# untitled.net
KiCad netlist of a schematic drawn in EAGLE
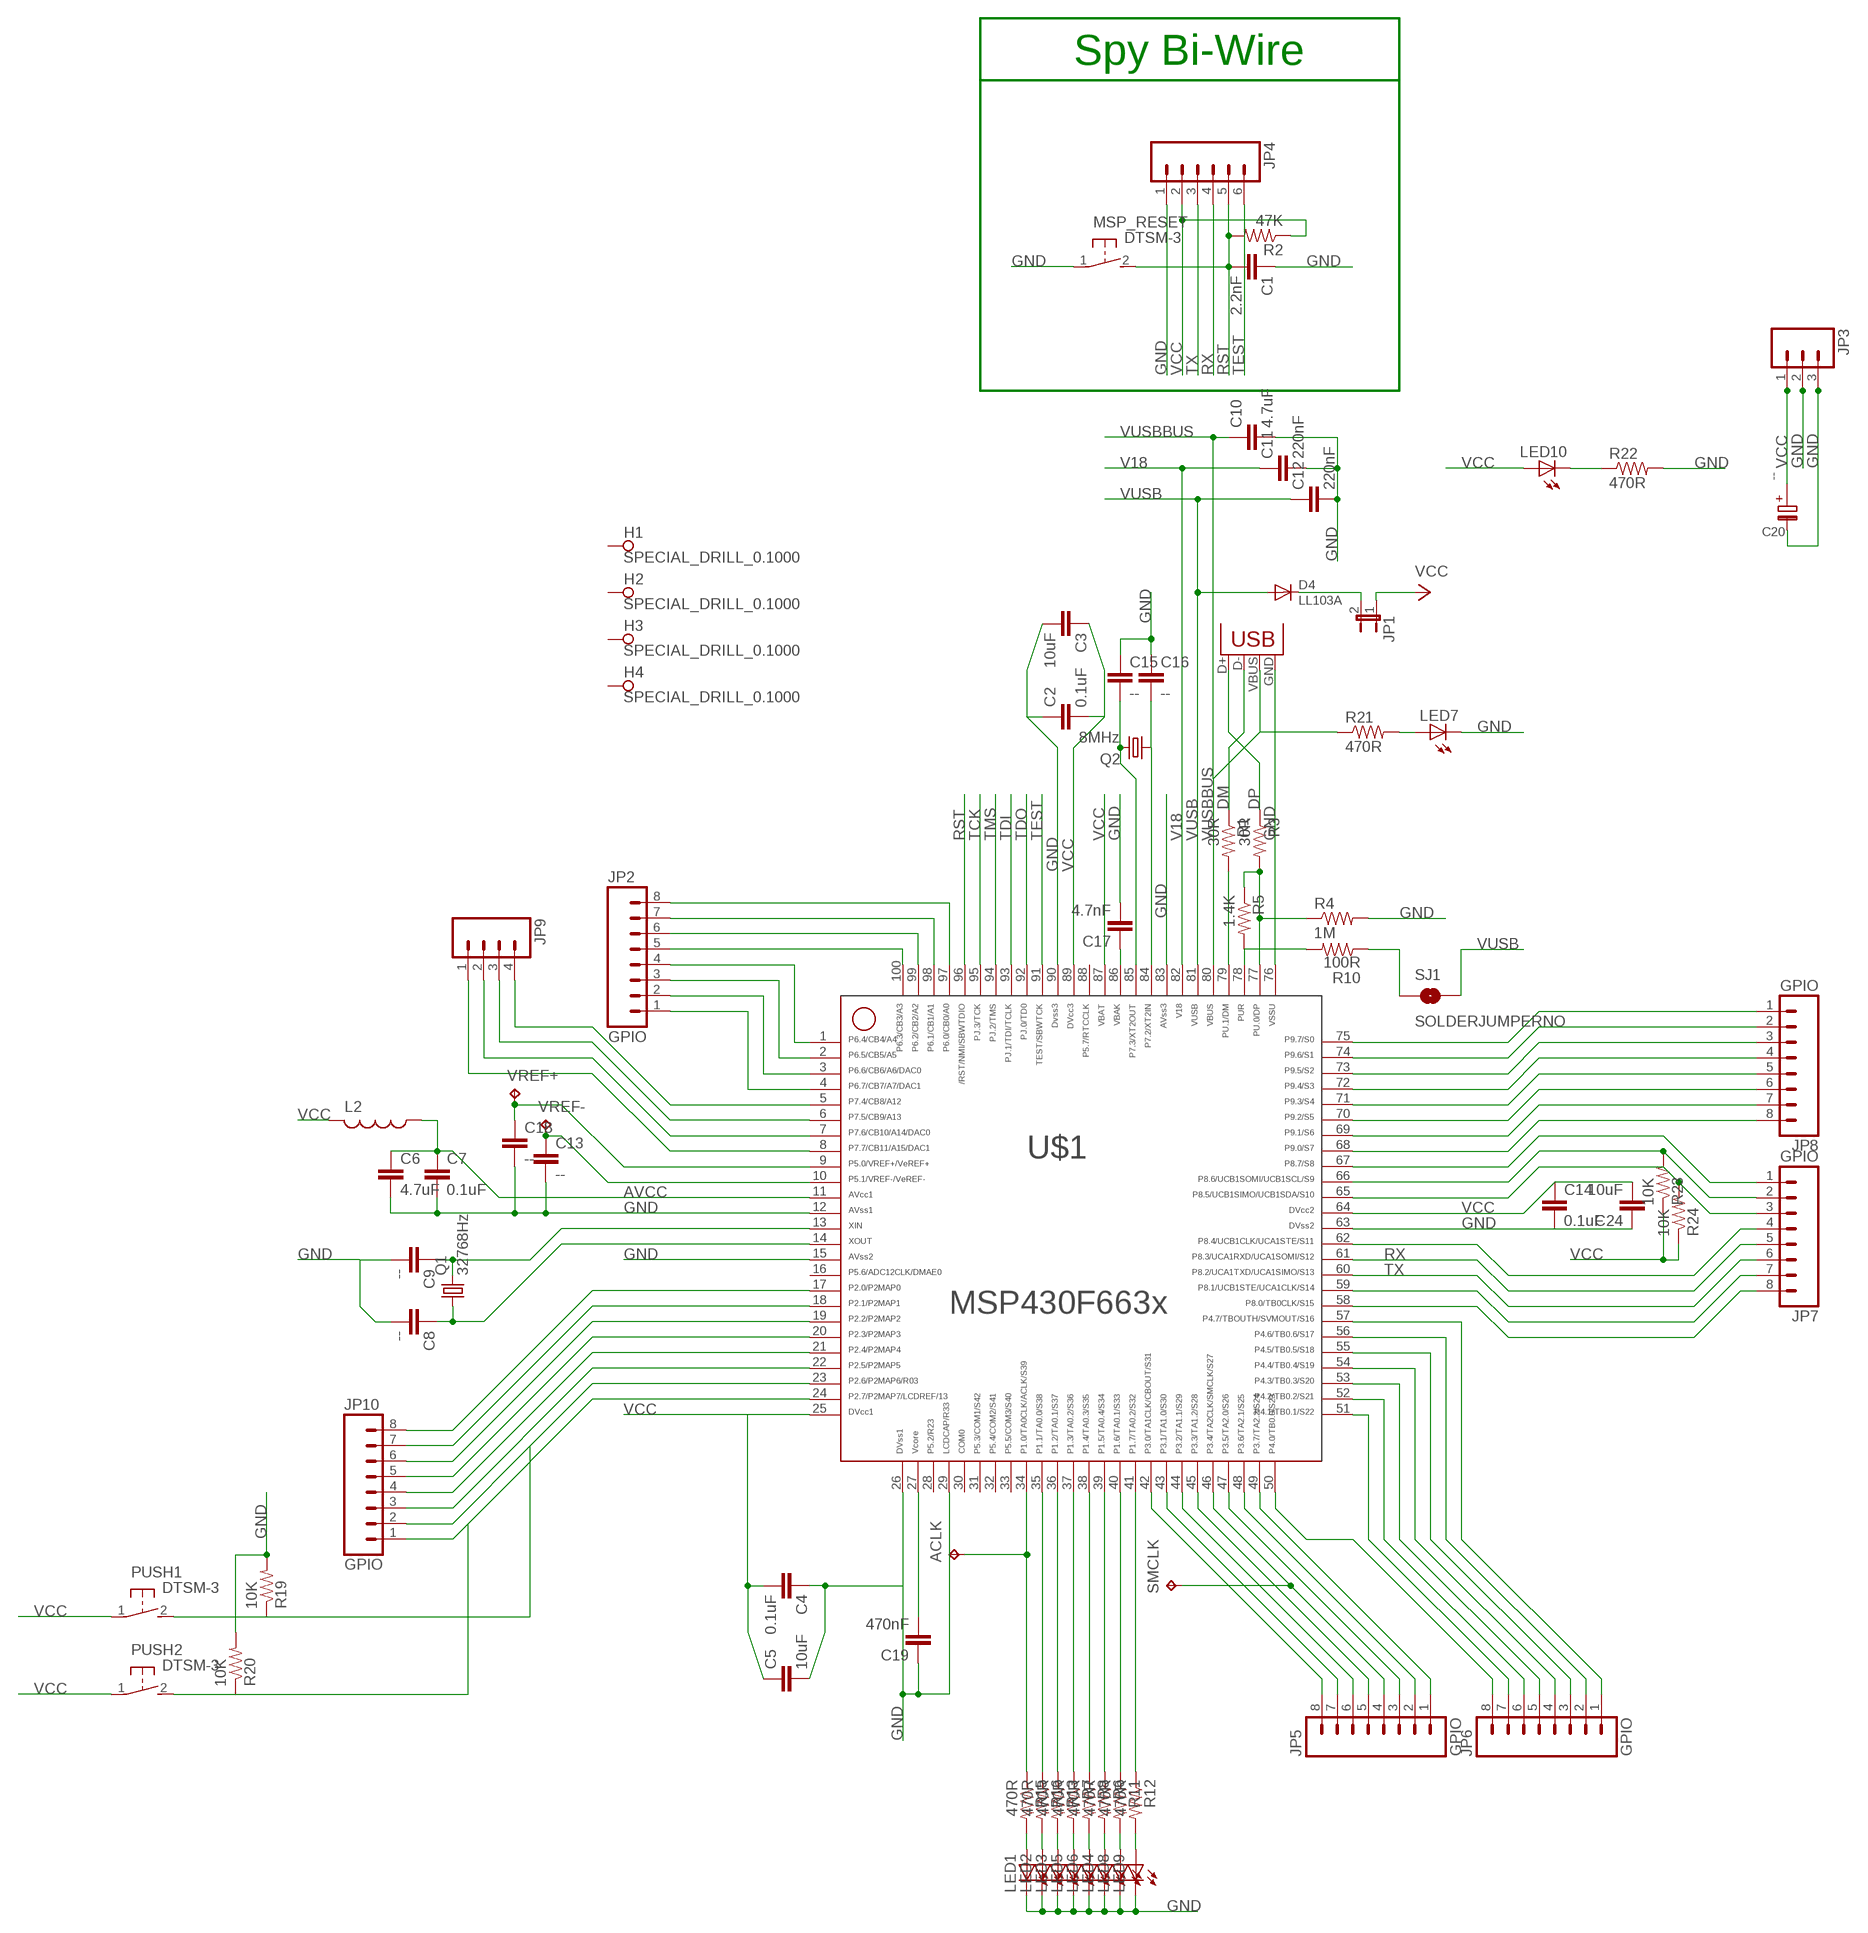
[diagram p0: schematic, sheet 1]

(export (version "E")
  (design (tool "Eeschema 10.0.6"))
  (components
    (comp (ref "ACLK")
      (value "TPB1,27")
      (footprint "eagle-import:B1,27")
      (libsource (lib "eagle-import") (part "TPB1,27"))
    )
    (comp (ref "C1")
      (value "2.2nF")
      (footprint "eagle-import:0805")
      (libsource (lib "eagle-import") (part "CAP0805"))
    )
    (comp (ref "C2")
      (value "0.1uF")
      (footprint "eagle-import:0805")
      (libsource (lib "eagle-import") (part "CAP0805"))
    )
    (comp (ref "C3")
      (value "10uF")
      (footprint "eagle-import:0805")
      (libsource (lib "eagle-import") (part "CAP0805"))
    )
    (comp (ref "C4")
      (value "0.1uF")
      (footprint "eagle-import:0805")
      (libsource (lib "eagle-import") (part "CAP0805"))
    )
    (comp (ref "C5")
      (value "10uF")
      (footprint "eagle-import:0805")
      (libsource (lib "eagle-import") (part "CAP0805"))
    )
    (comp (ref "C6")
      (value "4.7uF")
      (footprint "eagle-import:0805")
      (libsource (lib "eagle-import") (part "CAP0805"))
    )
    (comp (ref "C7")
      (value "0.1uF")
      (footprint "eagle-import:0805")
      (libsource (lib "eagle-import") (part "CAP0805"))
    )
    (comp (ref "C8")
      (value "--")
      (footprint "eagle-import:0805")
      (libsource (lib "eagle-import") (part "CAP0805"))
    )
    (comp (ref "C9")
      (value "--")
      (footprint "eagle-import:0805")
      (libsource (lib "eagle-import") (part "CAP0805"))
    )
    (comp (ref "C10")
      (value "4.7uF")
      (footprint "eagle-import:0805")
      (libsource (lib "eagle-import") (part "CAP0805"))
    )
    (comp (ref "C11")
      (value "220nF")
      (footprint "eagle-import:0805")
      (libsource (lib "eagle-import") (part "CAP0805"))
    )
    (comp (ref "C12")
      (value "220nF")
      (footprint "eagle-import:0805")
      (libsource (lib "eagle-import") (part "CAP0805"))
    )
    (comp (ref "C13")
      (value "--")
      (footprint "eagle-import:0805")
      (libsource (lib "eagle-import") (part "CAP0805"))
    )
    (comp (ref "C14")
      (value "0.1uF")
      (footprint "eagle-import:0805")
      (libsource (lib "eagle-import") (part "CAP0805"))
    )
    (comp (ref "C15")
      (value "--")
      (footprint "eagle-import:0805")
      (libsource (lib "eagle-import") (part "CAP0805"))
    )
    (comp (ref "C16")
      (value "--")
      (footprint "eagle-import:0805")
      (libsource (lib "eagle-import") (part "CAP0805"))
    )
    (comp (ref "C17")
      (value "4.7nF")
      (footprint "eagle-import:0805")
      (libsource (lib "eagle-import") (part "CAP0805"))
    )
    (comp (ref "C18")
      (value "--")
      (footprint "eagle-import:0805")
      (libsource (lib "eagle-import") (part "CAP0805"))
    )
    (comp (ref "C19")
      (value "470nF")
      (footprint "eagle-import:0805")
      (libsource (lib "eagle-import") (part "CAP0805"))
    )
    (comp (ref "C20")
      (value "--")
      (footprint "eagle-import:1210ELKO")
      (libsource (lib "eagle-import") (part "ELKO_1210"))
    )
    (comp (ref "C24")
      (value "10uF")
      (footprint "eagle-import:0805")
      (libsource (lib "eagle-import") (part "CAP0805"))
    )
    (comp (ref "D4")
      (value "LL103A")
      (footprint "eagle-import:SOD-80")
      (libsource (lib "eagle-import") (part "D"))
    )
    (comp (ref "H1")
      (value "SPECIAL_DRILL_0.1000")
      (footprint "eagle-import:PAD_0.1000")
      (libsource (lib "eagle-import") (part "SPECIAL_DRILL_0.1000"))
    )
    (comp (ref "H2")
      (value "SPECIAL_DRILL_0.1000")
      (footprint "eagle-import:PAD_0.1000")
      (libsource (lib "eagle-import") (part "SPECIAL_DRILL_0.1000"))
    )
    (comp (ref "H3")
      (value "SPECIAL_DRILL_0.1000")
      (footprint "eagle-import:PAD_0.1000")
      (libsource (lib "eagle-import") (part "SPECIAL_DRILL_0.1000"))
    )
    (comp (ref "H4")
      (value "SPECIAL_DRILL_0.1000")
      (footprint "eagle-import:PAD_0.1000")
      (libsource (lib "eagle-import") (part "SPECIAL_DRILL_0.1000"))
    )
    (comp (ref "JP1")
      (value "JP1E")
      (footprint "eagle-import:JP1")
      (libsource (lib "eagle-import") (part "JP1E"))
    )
    (comp (ref "JP2")
      (value "GPIO")
      (footprint "eagle-import:1X08")
      (libsource (lib "eagle-import") (part "M08"))
    )
    (comp (ref "JP3")
      (value "M03PTH")
      (footprint "eagle-import:1X03")
      (libsource (lib "eagle-import") (part "M03PTH"))
    )
    (comp (ref "JP4")
      (value "M06SIP")
      (footprint "eagle-import:1X06")
      (libsource (lib "eagle-import") (part "M06SIP"))
    )
    (comp (ref "JP5")
      (value "GPIO")
      (footprint "eagle-import:1X08")
      (libsource (lib "eagle-import") (part "M08"))
    )
    (comp (ref "JP6")
      (value "GPIO")
      (footprint "eagle-import:1X08")
      (libsource (lib "eagle-import") (part "M08"))
    )
    (comp (ref "JP7")
      (value "GPIO")
      (footprint "eagle-import:1X08")
      (libsource (lib "eagle-import") (part "M08"))
    )
    (comp (ref "JP8")
      (value "GPIO")
      (footprint "eagle-import:1X08")
      (libsource (lib "eagle-import") (part "M08"))
    )
    (comp (ref "JP9")
      (value "M04PTH")
      (footprint "eagle-import:1X04")
      (libsource (lib "eagle-import") (part "M04PTH"))
    )
    (comp (ref "JP10")
      (value "GPIO")
      (footprint "eagle-import:1X08")
      (libsource (lib "eagle-import") (part "M08"))
    )
    (comp (ref "L2")
      (value "L-USL2012C")
      (footprint "eagle-import:L2012C")
      (libsource (lib "eagle-import") (part "L-USL2012C"))
    )
    (comp (ref "LED1")
      (value "LEDCHIPLED_0805")
      (footprint "eagle-import:CHIPLED_0805")
      (libsource (lib "eagle-import") (part "LEDCHIPLED_0805"))
    )
    (comp (ref "LED2")
      (value "LEDCHIPLED_0805")
      (footprint "eagle-import:CHIPLED_0805")
      (libsource (lib "eagle-import") (part "LEDCHIPLED_0805"))
    )
    (comp (ref "LED3")
      (value "LEDCHIPLED_0805")
      (footprint "eagle-import:CHIPLED_0805")
      (libsource (lib "eagle-import") (part "LEDCHIPLED_0805"))
    )
    (comp (ref "LED4")
      (value "LEDCHIPLED_0805")
      (footprint "eagle-import:CHIPLED_0805")
      (libsource (lib "eagle-import") (part "LEDCHIPLED_0805"))
    )
    (comp (ref "LED5")
      (value "LEDCHIPLED_0805")
      (footprint "eagle-import:CHIPLED_0805")
      (libsource (lib "eagle-import") (part "LEDCHIPLED_0805"))
    )
    (comp (ref "LED6")
      (value "LEDCHIPLED_0805")
      (footprint "eagle-import:CHIPLED_0805")
      (libsource (lib "eagle-import") (part "LEDCHIPLED_0805"))
    )
    (comp (ref "LED7")
      (value "LEDCHIPLED_0805")
      (footprint "eagle-import:CHIPLED_0805")
      (libsource (lib "eagle-import") (part "LEDCHIPLED_0805"))
    )
    (comp (ref "LED8")
      (value "LEDCHIPLED_0805")
      (footprint "eagle-import:CHIPLED_0805")
      (libsource (lib "eagle-import") (part "LEDCHIPLED_0805"))
    )
    (comp (ref "LED9")
      (value "LEDCHIPLED_0805")
      (footprint "eagle-import:CHIPLED_0805")
      (libsource (lib "eagle-import") (part "LEDCHIPLED_0805"))
    )
    (comp (ref "LED10")
      (value "LEDCHIPLED_0805")
      (footprint "eagle-import:CHIPLED_0805")
      (libsource (lib "eagle-import") (part "LEDCHIPLED_0805"))
    )
    (comp (ref "MSP_RESET")
      (value "DTSM-3")
      (footprint "eagle-import:DTSM-3")
      (libsource (lib "eagle-import") (part "DTSM-3"))
    )
    (comp (ref "PUSH1")
      (value "DTSM-3")
      (footprint "eagle-import:DTSM-3")
      (libsource (lib "eagle-import") (part "DTSM-3"))
    )
    (comp (ref "PUSH2")
      (value "DTSM-3")
      (footprint "eagle-import:DTSM-3")
      (libsource (lib "eagle-import") (part "DTSM-3"))
    )
    (comp (ref "Q1")
      (value "32768Hz")
      (footprint "eagle-import:TC26H")
      (libsource (lib "eagle-import") (part "CRYSTALTC26H"))
    )
    (comp (ref "Q2")
      (value "8MHz")
      (footprint "eagle-import:HC49U-V")
      (libsource (lib "eagle-import") (part "CRYSTALHC49U-V"))
    )
    (comp (ref "R1")
      (value "30R")
      (footprint "eagle-import:M0805")
      (libsource (lib "eagle-import") (part "resistor_R-US_M0805"))
    )
    (comp (ref "R2")
      (value "47K")
      (footprint "eagle-import:M0805")
      (libsource (lib "eagle-import") (part "resistor_R-US_M0805"))
    )
    (comp (ref "R3")
      (value "30R")
      (footprint "eagle-import:M0805")
      (libsource (lib "eagle-import") (part "resistor_R-US_M0805"))
    )
    (comp (ref "R4")
      (value "1M")
      (footprint "eagle-import:M0805")
      (libsource (lib "eagle-import") (part "resistor_R-US_M0805"))
    )
    (comp (ref "R5")
      (value "1.4K")
      (footprint "eagle-import:M0805")
      (libsource (lib "eagle-import") (part "resistor_R-US_M0805"))
    )
    (comp (ref "R6")
      (value "470R")
      (footprint "eagle-import:R0603")
      (libsource (lib "eagle-import") (part "R-US_R0603"))
    )
    (comp (ref "R7")
      (value "470R")
      (footprint "eagle-import:R0603")
      (libsource (lib "eagle-import") (part "R-US_R0603"))
    )
    (comp (ref "R8")
      (value "470R")
      (footprint "eagle-import:R0603")
      (libsource (lib "eagle-import") (part "R-US_R0603"))
    )
    (comp (ref "R10")
      (value "100R")
      (footprint "eagle-import:R0603")
      (libsource (lib "eagle-import") (part "rcl_R-US_R0603"))
    )
    (comp (ref "R11")
      (value "470R")
      (footprint "eagle-import:R0603")
      (libsource (lib "eagle-import") (part "R-US_R0603"))
    )
    (comp (ref "R12")
      (value "470R")
      (footprint "eagle-import:R0603")
      (libsource (lib "eagle-import") (part "R-US_R0603"))
    )
    (comp (ref "R13")
      (value "470R")
      (footprint "eagle-import:R0603")
      (libsource (lib "eagle-import") (part "R-US_R0603"))
    )
    (comp (ref "R15")
      (value "470R")
      (footprint "eagle-import:R0603")
      (libsource (lib "eagle-import") (part "R-US_R0603"))
    )
    (comp (ref "R16")
      (value "470R")
      (footprint "eagle-import:R0603")
      (libsource (lib "eagle-import") (part "R-US_R0603"))
    )
    (comp (ref "R19")
      (value "10K")
      (footprint "eagle-import:M0805")
      (libsource (lib "eagle-import") (part "resistor_R-US_M0805"))
    )
    (comp (ref "R20")
      (value "10K")
      (footprint "eagle-import:M0805")
      (libsource (lib "eagle-import") (part "resistor_R-US_M0805"))
    )
    (comp (ref "R21")
      (value "470R")
      (footprint "eagle-import:R0603")
      (libsource (lib "eagle-import") (part "R-US_R0603"))
    )
    (comp (ref "R22")
      (value "470R")
      (footprint "eagle-import:R0603")
      (libsource (lib "eagle-import") (part "R-US_R0603"))
    )
    (comp (ref "R23")
      (value "10K")
      (footprint "eagle-import:M0805")
      (libsource (lib "eagle-import") (part "resistor_R-US_M0805"))
    )
    (comp (ref "R24")
      (value "10K")
      (footprint "eagle-import:M0805")
      (libsource (lib "eagle-import") (part "resistor_R-US_M0805"))
    )
    (comp (ref "SJ1")
      (value "SOLDERJUMPERNO")
      (footprint "eagle-import:SJ_2S-NO")
      (libsource (lib "eagle-import") (part "SOLDERJUMPERNO"))
    )
    (comp (ref "SMCLK")
      (value "TPB1,27")
      (footprint "eagle-import:B1,27")
      (libsource (lib "eagle-import") (part "TPB1,27"))
    )
    (comp (ref "U$1")
      (value "F66XX---PZ100")
      (footprint "eagle-import:PZ100")
      (libsource (lib "eagle-import") (part "F66XX---PZ100"))
    )
    (comp (ref "VREF+")
      (value "TPB1,27")
      (footprint "eagle-import:B1,27")
      (libsource (lib "eagle-import") (part "TPB1,27"))
    )
    (comp (ref "VREF-")
      (value "TPB1,27")
      (footprint "eagle-import:B1,27")
      (libsource (lib "eagle-import") (part "TPB1,27"))
    )
    (comp (ref "X1")
      (value "USBSMD")
      (footprint "eagle-import:USB-MINIB")
      (libsource (lib "eagle-import") (part "USBSMD"))
    )
  )
  (nets
    (net (code "1") (name "/AVCC") (class "Default")
      (node (ref "C6") (pin "1") (pinfunction "1_1") (pintype "passive"))
      (node (ref "C7") (pin "1") (pinfunction "1_1") (pintype "passive"))
      (node (ref "L2") (pin "1") (pinfunction "1_1") (pintype "passive"))
      (node (ref "U$1") (pin "11") (pinfunction "11_11") (pintype "power_in"))
    )
    (net (code "2") (name "/DM") (class "Default")
      (node (ref "R1") (pin "1") (pinfunction "1_1") (pintype "passive"))
      (node (ref "X1") (pin "D-") (pinfunction "D-_D-") (pintype "bidirectional"))
    )
    (net (code "3") (name "/DP") (class "Default")
      (node (ref "R3") (pin "1") (pinfunction "1_1") (pintype "passive"))
      (node (ref "X1") (pin "D+") (pinfunction "D+_D+") (pintype "bidirectional"))
    )
    (net (code "4") (name "/GND") (class "Default")
      (node (ref "C1") (pin "1") (pinfunction "1_1") (pintype "passive"))
      (node (ref "C10") (pin "2") (pinfunction "2_2") (pintype "passive"))
      (node (ref "C11") (pin "2") (pinfunction "2_2") (pintype "passive"))
      (node (ref "C12") (pin "2") (pinfunction "2_2") (pintype "passive"))
      (node (ref "C13") (pin "2") (pinfunction "2_2") (pintype "passive"))
      (node (ref "C14") (pin "2") (pinfunction "2_2") (pintype "passive"))
      (node (ref "C15") (pin "1") (pinfunction "1_1") (pintype "passive"))
      (node (ref "C16") (pin "1") (pinfunction "1_1") (pintype "passive"))
      (node (ref "C17") (pin "2") (pinfunction "2_2") (pintype "passive"))
      (node (ref "C18") (pin "2") (pinfunction "2_2") (pintype "passive"))
      (node (ref "C19") (pin "1") (pinfunction "1_1") (pintype "passive"))
      (node (ref "C2") (pin "1") (pinfunction "1_1") (pintype "passive"))
      (node (ref "C20") (pin "-") (pinfunction "-_-") (pintype "passive"))
      (node (ref "C24") (pin "1") (pinfunction "1_1") (pintype "passive"))
      (node (ref "C3") (pin "2") (pinfunction "2_2") (pintype "passive"))
      (node (ref "C4") (pin "1") (pinfunction "1_1") (pintype "passive"))
      (node (ref "C5") (pin "2") (pinfunction "2_2") (pintype "passive"))
      (node (ref "C6") (pin "2") (pinfunction "2_2") (pintype "passive"))
      (node (ref "C7") (pin "2") (pinfunction "2_2") (pintype "passive"))
      (node (ref "C8") (pin "2") (pinfunction "2_2") (pintype "passive"))
      (node (ref "C9") (pin "2") (pinfunction "2_2") (pintype "passive"))
      (node (ref "JP3") (pin "2") (pinfunction "2_2") (pintype "passive"))
      (node (ref "JP3") (pin "3") (pinfunction "3_3") (pintype "passive"))
      (node (ref "JP4") (pin "1") (pinfunction "1_1") (pintype "passive"))
      (node (ref "LED1") (pin "C") (pinfunction "C_C") (pintype "passive"))
      (node (ref "LED2") (pin "C") (pinfunction "C_C") (pintype "passive"))
      (node (ref "LED3") (pin "C") (pinfunction "C_C") (pintype "passive"))
      (node (ref "LED4") (pin "C") (pinfunction "C_C") (pintype "passive"))
      (node (ref "LED5") (pin "C") (pinfunction "C_C") (pintype "passive"))
      (node (ref "LED6") (pin "C") (pinfunction "C_C") (pintype "passive"))
      (node (ref "LED7") (pin "C") (pinfunction "C_C") (pintype "passive"))
      (node (ref "LED8") (pin "C") (pinfunction "C_C") (pintype "passive"))
      (node (ref "LED9") (pin "C") (pinfunction "C_C") (pintype "passive"))
      (node (ref "MSP_RESET") (pin "1") (pinfunction "1_1") (pintype "passive"))
      (node (ref "R19") (pin "2") (pinfunction "2_2") (pintype "passive"))
      (node (ref "R20") (pin "2") (pinfunction "2_2") (pintype "passive"))
      (node (ref "R22") (pin "2") (pinfunction "2_2") (pintype "passive"))
      (node (ref "R4") (pin "2") (pinfunction "2_2") (pintype "passive"))
      (node (ref "U$1") (pin "12") (pinfunction "12_12") (pintype "power_in"))
      (node (ref "U$1") (pin "15") (pinfunction "15_15") (pintype "power_in"))
      (node (ref "U$1") (pin "26") (pinfunction "26_26") (pintype "power_in"))
      (node (ref "U$1") (pin "29") (pinfunction "29_29") (pintype "bidirectional"))
      (node (ref "U$1") (pin "63") (pinfunction "63_63") (pintype "power_in"))
      (node (ref "U$1") (pin "76") (pinfunction "76_76") (pintype "bidirectional"))
      (node (ref "U$1") (pin "83") (pinfunction "83_83") (pintype "power_in"))
      (node (ref "U$1") (pin "90") (pinfunction "90_90") (pintype "power_in"))
      (node (ref "X1") (pin "GND") (pinfunction "GND_GND") (pintype "bidirectional"))
    )
    (net (code "5") (name "/RST") (class "Default")
      (node (ref "C1") (pin "2") (pinfunction "2_2") (pintype "passive"))
      (node (ref "JP4") (pin "5") (pinfunction "5_5") (pintype "passive"))
      (node (ref "MSP_RESET") (pin "2") (pinfunction "2_2") (pintype "passive"))
      (node (ref "R2") (pin "2") (pinfunction "2_2") (pintype "passive"))
      (node (ref "U$1") (pin "96") (pinfunction "96_96") (pintype "bidirectional"))
    )
    (net (code "6") (name "/RX") (class "Default")
      (node (ref "JP4") (pin "4") (pinfunction "4_4") (pintype "passive"))
      (node (ref "JP7") (pin "5") (pinfunction "5_5") (pintype "passive"))
      (node (ref "U$1") (pin "61") (pinfunction "61_61") (pintype "bidirectional"))
    )
    (net (code "7") (name "/TCK") (class "Default")
      (node (ref "U$1") (pin "95") (pinfunction "95_95") (pintype "bidirectional"))
    )
    (net (code "8") (name "/TDI") (class "Default")
      (node (ref "U$1") (pin "93") (pinfunction "93_93") (pintype "bidirectional"))
    )
    (net (code "9") (name "/TDO") (class "Default")
      (node (ref "U$1") (pin "92") (pinfunction "92_92") (pintype "bidirectional"))
    )
    (net (code "10") (name "/TEST") (class "Default")
      (node (ref "JP4") (pin "6") (pinfunction "6_6") (pintype "passive"))
      (node (ref "U$1") (pin "91") (pinfunction "91_91") (pintype "input"))
    )
    (net (code "11") (name "/TMS") (class "Default")
      (node (ref "U$1") (pin "94") (pinfunction "94_94") (pintype "bidirectional"))
    )
    (net (code "12") (name "/TX") (class "Default")
      (node (ref "JP4") (pin "3") (pinfunction "3_3") (pintype "passive"))
      (node (ref "JP7") (pin "6") (pinfunction "6_6") (pintype "passive"))
      (node (ref "U$1") (pin "60") (pinfunction "60_60") (pintype "bidirectional"))
    )
    (net (code "13") (name "/V18") (class "Default")
      (node (ref "C11") (pin "1") (pinfunction "1_1") (pintype "passive"))
      (node (ref "U$1") (pin "82") (pinfunction "82_82") (pintype "bidirectional"))
    )
    (net (code "14") (name "/VUSB") (class "Default")
      (node (ref "C12") (pin "1") (pinfunction "1_1") (pintype "passive"))
      (node (ref "D4") (pin "1") (pinfunction "A_1") (pintype "passive"))
      (node (ref "SJ1") (pin "2") (pinfunction "2_2") (pintype "passive"))
      (node (ref "U$1") (pin "81") (pinfunction "81_81") (pintype "bidirectional"))
    )
    (net (code "15") (name "/VUSBBUS") (class "Default")
      (node (ref "C10") (pin "1") (pinfunction "1_1") (pintype "passive"))
      (node (ref "R21") (pin "1") (pinfunction "1_1") (pintype "passive"))
      (node (ref "U$1") (pin "80") (pinfunction "80_80") (pintype "bidirectional"))
      (node (ref "X1") (pin "VBUS") (pinfunction "VBUS_VBUS") (pintype "bidirectional"))
    )
    (net (code "16") (name "Net-(ACLK-PadTP)") (class "Default")
      (node (ref "ACLK") (pin "TP") (pinfunction "TP_TP") (pintype "input"))
      (node (ref "R15") (pin "1") (pinfunction "1_1") (pintype "passive"))
      (node (ref "U$1") (pin "34") (pinfunction "34_34") (pintype "bidirectional"))
    )
    (net (code "17") (name "Net-(C8-Pad1)") (class "Default")
      (node (ref "C8") (pin "1") (pinfunction "1_1") (pintype "passive"))
      (node (ref "Q1") (pin "1") (pinfunction "1_1") (pintype "passive"))
      (node (ref "U$1") (pin "14") (pinfunction "14_14") (pintype "output"))
    )
    (net (code "18") (name "Net-(C9-Pad1)") (class "Default")
      (node (ref "C9") (pin "1") (pinfunction "1_1") (pintype "passive"))
      (node (ref "Q1") (pin "2") (pinfunction "2_2") (pintype "passive"))
      (node (ref "U$1") (pin "13") (pinfunction "13_13") (pintype "input"))
    )
    (net (code "19") (name "Net-(C13-Pad1)") (class "Default")
      (node (ref "C13") (pin "1") (pinfunction "1_1") (pintype "passive"))
      (node (ref "U$1") (pin "10") (pinfunction "10_10") (pintype "bidirectional"))
      (node (ref "VREF-") (pin "TP") (pinfunction "TP_TP") (pintype "input"))
    )
    (net (code "20") (name "Net-(C15-Pad2)") (class "Default")
      (node (ref "C15") (pin "2") (pinfunction "2_2") (pintype "passive"))
      (node (ref "Q2") (pin "2") (pinfunction "2_2") (pintype "passive"))
      (node (ref "U$1") (pin "85") (pinfunction "85_85") (pintype "bidirectional"))
    )
    (net (code "21") (name "Net-(C16-Pad2)") (class "Default")
      (node (ref "C16") (pin "2") (pinfunction "2_2") (pintype "passive"))
      (node (ref "Q2") (pin "1") (pinfunction "1_1") (pintype "passive"))
      (node (ref "U$1") (pin "84") (pinfunction "84_84") (pintype "bidirectional"))
    )
    (net (code "22") (name "Net-(C17-Pad1)") (class "Default")
      (node (ref "C17") (pin "1") (pinfunction "1_1") (pintype "passive"))
      (node (ref "U$1") (pin "86") (pinfunction "86_86") (pintype "bidirectional"))
    )
    (net (code "23") (name "Net-(C18-Pad1)") (class "Default")
      (node (ref "C18") (pin "1") (pinfunction "1_1") (pintype "passive"))
      (node (ref "U$1") (pin "9") (pinfunction "9_9") (pintype "bidirectional"))
      (node (ref "VREF+") (pin "TP") (pinfunction "TP_TP") (pintype "input"))
    )
    (net (code "24") (name "Net-(C19-Pad2)") (class "Default")
      (node (ref "C19") (pin "2") (pinfunction "2_2") (pintype "passive"))
      (node (ref "U$1") (pin "27") (pinfunction "27_27") (pintype "bidirectional"))
    )
    (net (code "25") (name "Net-(D4-K)") (class "Default")
      (node (ref "D4") (pin "2") (pinfunction "K_2") (pintype "passive"))
      (node (ref "JP1") (pin "2") (pinfunction "2_2") (pintype "passive"))
    )
    (net (code "26") (name "Net-(JP2-Pad1)") (class "Default")
      (node (ref "JP2") (pin "1") (pinfunction "1_1") (pintype "passive"))
      (node (ref "U$1") (pin "4") (pinfunction "4_4") (pintype "bidirectional"))
    )
    (net (code "27") (name "Net-(JP2-Pad2)") (class "Default")
      (node (ref "JP2") (pin "2") (pinfunction "2_2") (pintype "passive"))
      (node (ref "U$1") (pin "3") (pinfunction "3_3") (pintype "bidirectional"))
    )
    (net (code "28") (name "Net-(JP2-Pad3)") (class "Default")
      (node (ref "JP2") (pin "3") (pinfunction "3_3") (pintype "passive"))
      (node (ref "U$1") (pin "2") (pinfunction "2_2") (pintype "bidirectional"))
    )
    (net (code "29") (name "Net-(JP2-Pad4)") (class "Default")
      (node (ref "JP2") (pin "4") (pinfunction "4_4") (pintype "passive"))
      (node (ref "U$1") (pin "1") (pinfunction "1_1") (pintype "bidirectional"))
    )
    (net (code "30") (name "Net-(JP2-Pad5)") (class "Default")
      (node (ref "JP2") (pin "5") (pinfunction "5_5") (pintype "passive"))
      (node (ref "U$1") (pin "100") (pinfunction "100_100") (pintype "bidirectional"))
    )
    (net (code "31") (name "Net-(JP2-Pad6)") (class "Default")
      (node (ref "JP2") (pin "6") (pinfunction "6_6") (pintype "passive"))
      (node (ref "U$1") (pin "99") (pinfunction "99_99") (pintype "bidirectional"))
    )
    (net (code "32") (name "Net-(JP2-Pad7)") (class "Default")
      (node (ref "JP2") (pin "7") (pinfunction "7_7") (pintype "passive"))
      (node (ref "U$1") (pin "98") (pinfunction "98_98") (pintype "bidirectional"))
    )
    (net (code "33") (name "Net-(JP2-Pad8)") (class "Default")
      (node (ref "JP2") (pin "8") (pinfunction "8_8") (pintype "passive"))
      (node (ref "U$1") (pin "97") (pinfunction "97_97") (pintype "bidirectional"))
    )
    (net (code "34") (name "Net-(JP5-Pad1)") (class "Default")
      (node (ref "JP5") (pin "1") (pinfunction "1_1") (pintype "passive"))
      (node (ref "U$1") (pin "49") (pinfunction "49_49") (pintype "bidirectional"))
    )
    (net (code "35") (name "Net-(JP5-Pad2)") (class "Default")
      (node (ref "JP5") (pin "2") (pinfunction "2_2") (pintype "passive"))
      (node (ref "U$1") (pin "48") (pinfunction "48_48") (pintype "bidirectional"))
    )
    (net (code "36") (name "Net-(JP5-Pad3)") (class "Default")
      (node (ref "JP5") (pin "3") (pinfunction "3_3") (pintype "passive"))
      (node (ref "U$1") (pin "47") (pinfunction "47_47") (pintype "bidirectional"))
    )
    (net (code "37") (name "Net-(JP5-Pad4)") (class "Default")
      (node (ref "JP5") (pin "4") (pinfunction "4_4") (pintype "passive"))
      (node (ref "SMCLK") (pin "TP") (pinfunction "TP_TP") (pintype "input"))
      (node (ref "U$1") (pin "46") (pinfunction "46_46") (pintype "bidirectional"))
    )
    (net (code "38") (name "Net-(JP5-Pad5)") (class "Default")
      (node (ref "JP5") (pin "5") (pinfunction "5_5") (pintype "passive"))
      (node (ref "U$1") (pin "45") (pinfunction "45_45") (pintype "bidirectional"))
    )
    (net (code "39") (name "Net-(JP5-Pad6)") (class "Default")
      (node (ref "JP5") (pin "6") (pinfunction "6_6") (pintype "passive"))
      (node (ref "U$1") (pin "44") (pinfunction "44_44") (pintype "bidirectional"))
    )
    (net (code "40") (name "Net-(JP5-Pad7)") (class "Default")
      (node (ref "JP5") (pin "7") (pinfunction "7_7") (pintype "passive"))
      (node (ref "U$1") (pin "43") (pinfunction "43_43") (pintype "bidirectional"))
    )
    (net (code "41") (name "Net-(JP5-Pad8)") (class "Default")
      (node (ref "JP5") (pin "8") (pinfunction "8_8") (pintype "passive"))
      (node (ref "U$1") (pin "42") (pinfunction "42_42") (pintype "bidirectional"))
    )
    (net (code "42") (name "Net-(JP6-Pad1)") (class "Default")
      (node (ref "JP6") (pin "1") (pinfunction "1_1") (pintype "passive"))
      (node (ref "U$1") (pin "57") (pinfunction "57_57") (pintype "bidirectional"))
    )
    (net (code "43") (name "Net-(JP6-Pad2)") (class "Default")
      (node (ref "JP6") (pin "2") (pinfunction "2_2") (pintype "passive"))
      (node (ref "U$1") (pin "56") (pinfunction "56_56") (pintype "bidirectional"))
    )
    (net (code "44") (name "Net-(JP6-Pad3)") (class "Default")
      (node (ref "JP6") (pin "3") (pinfunction "3_3") (pintype "passive"))
      (node (ref "U$1") (pin "55") (pinfunction "55_55") (pintype "bidirectional"))
    )
    (net (code "45") (name "Net-(JP6-Pad4)") (class "Default")
      (node (ref "JP6") (pin "4") (pinfunction "4_4") (pintype "passive"))
      (node (ref "U$1") (pin "54") (pinfunction "54_54") (pintype "bidirectional"))
    )
    (net (code "46") (name "Net-(JP6-Pad5)") (class "Default")
      (node (ref "JP6") (pin "5") (pinfunction "5_5") (pintype "passive"))
      (node (ref "U$1") (pin "53") (pinfunction "53_53") (pintype "bidirectional"))
    )
    (net (code "47") (name "Net-(JP6-Pad6)") (class "Default")
      (node (ref "JP6") (pin "6") (pinfunction "6_6") (pintype "passive"))
      (node (ref "U$1") (pin "52") (pinfunction "52_52") (pintype "bidirectional"))
    )
    (net (code "48") (name "Net-(JP6-Pad7)") (class "Default")
      (node (ref "JP6") (pin "7") (pinfunction "7_7") (pintype "passive"))
      (node (ref "U$1") (pin "51") (pinfunction "51_51") (pintype "bidirectional"))
    )
    (net (code "49") (name "Net-(JP6-Pad8)") (class "Default")
      (node (ref "JP6") (pin "8") (pinfunction "8_8") (pintype "passive"))
      (node (ref "U$1") (pin "50") (pinfunction "50_50") (pintype "bidirectional"))
    )
    (net (code "50") (name "Net-(JP7-Pad1)") (class "Default")
      (node (ref "JP7") (pin "1") (pinfunction "1_1") (pintype "passive"))
      (node (ref "U$1") (pin "67") (pinfunction "67_67") (pintype "bidirectional"))
    )
    (net (code "51") (name "Net-(JP7-Pad2)") (class "Default")
      (node (ref "JP7") (pin "2") (pinfunction "2_2") (pintype "passive"))
      (node (ref "R23") (pin "2") (pinfunction "2_2") (pintype "passive"))
      (node (ref "U$1") (pin "66") (pinfunction "66_66") (pintype "bidirectional"))
    )
    (net (code "52") (name "Net-(JP7-Pad3)") (class "Default")
      (node (ref "JP7") (pin "3") (pinfunction "3_3") (pintype "passive"))
      (node (ref "R24") (pin "2") (pinfunction "2_2") (pintype "passive"))
      (node (ref "U$1") (pin "65") (pinfunction "65_65") (pintype "bidirectional"))
    )
    (net (code "53") (name "Net-(JP7-Pad4)") (class "Default")
      (node (ref "JP7") (pin "4") (pinfunction "4_4") (pintype "passive"))
      (node (ref "U$1") (pin "62") (pinfunction "62_62") (pintype "bidirectional"))
    )
    (net (code "54") (name "Net-(JP7-Pad7)") (class "Default")
      (node (ref "JP7") (pin "7") (pinfunction "7_7") (pintype "passive"))
      (node (ref "U$1") (pin "59") (pinfunction "59_59") (pintype "bidirectional"))
    )
    (net (code "55") (name "Net-(JP7-Pad8)") (class "Default")
      (node (ref "JP7") (pin "8") (pinfunction "8_8") (pintype "passive"))
      (node (ref "U$1") (pin "58") (pinfunction "58_58") (pintype "bidirectional"))
    )
    (net (code "56") (name "Net-(JP8-Pad1)") (class "Default")
      (node (ref "JP8") (pin "1") (pinfunction "1_1") (pintype "passive"))
      (node (ref "U$1") (pin "75") (pinfunction "75_75") (pintype "bidirectional"))
    )
    (net (code "57") (name "Net-(JP8-Pad2)") (class "Default")
      (node (ref "JP8") (pin "2") (pinfunction "2_2") (pintype "passive"))
      (node (ref "U$1") (pin "74") (pinfunction "74_74") (pintype "bidirectional"))
    )
    (net (code "58") (name "Net-(JP8-Pad3)") (class "Default")
      (node (ref "JP8") (pin "3") (pinfunction "3_3") (pintype "passive"))
      (node (ref "U$1") (pin "73") (pinfunction "73_73") (pintype "bidirectional"))
    )
    (net (code "59") (name "Net-(JP8-Pad4)") (class "Default")
      (node (ref "JP8") (pin "4") (pinfunction "4_4") (pintype "passive"))
      (node (ref "U$1") (pin "72") (pinfunction "72_72") (pintype "bidirectional"))
    )
    (net (code "60") (name "Net-(JP8-Pad5)") (class "Default")
      (node (ref "JP8") (pin "5") (pinfunction "5_5") (pintype "passive"))
      (node (ref "U$1") (pin "71") (pinfunction "71_71") (pintype "bidirectional"))
    )
    (net (code "61") (name "Net-(JP8-Pad6)") (class "Default")
      (node (ref "JP8") (pin "6") (pinfunction "6_6") (pintype "passive"))
      (node (ref "U$1") (pin "70") (pinfunction "70_70") (pintype "bidirectional"))
    )
    (net (code "62") (name "Net-(JP8-Pad7)") (class "Default")
      (node (ref "JP8") (pin "7") (pinfunction "7_7") (pintype "passive"))
      (node (ref "U$1") (pin "69") (pinfunction "69_69") (pintype "bidirectional"))
    )
    (net (code "63") (name "Net-(JP8-Pad8)") (class "Default")
      (node (ref "JP8") (pin "8") (pinfunction "8_8") (pintype "passive"))
      (node (ref "U$1") (pin "68") (pinfunction "68_68") (pintype "bidirectional"))
    )
    (net (code "64") (name "Net-(JP9-Pad1)") (class "Default")
      (node (ref "JP9") (pin "1") (pinfunction "1_1") (pintype "passive"))
      (node (ref "U$1") (pin "8") (pinfunction "8_8") (pintype "bidirectional"))
    )
    (net (code "65") (name "Net-(JP9-Pad2)") (class "Default")
      (node (ref "JP9") (pin "2") (pinfunction "2_2") (pintype "passive"))
      (node (ref "U$1") (pin "7") (pinfunction "7_7") (pintype "bidirectional"))
    )
    (net (code "66") (name "Net-(JP9-Pad3)") (class "Default")
      (node (ref "JP9") (pin "3") (pinfunction "3_3") (pintype "passive"))
      (node (ref "U$1") (pin "6") (pinfunction "6_6") (pintype "bidirectional"))
    )
    (net (code "67") (name "Net-(JP9-Pad4)") (class "Default")
      (node (ref "JP9") (pin "4") (pinfunction "4_4") (pintype "passive"))
      (node (ref "U$1") (pin "5") (pinfunction "5_5") (pintype "bidirectional"))
    )
    (net (code "68") (name "Net-(JP10-Pad1)") (class "Default")
      (node (ref "JP10") (pin "1") (pinfunction "1_1") (pintype "passive"))
      (node (ref "PUSH2") (pin "2") (pinfunction "2_2") (pintype "passive"))
      (node (ref "R20") (pin "1") (pinfunction "1_1") (pintype "passive"))
      (node (ref "U$1") (pin "24") (pinfunction "24_24") (pintype "bidirectional"))
    )
    (net (code "69") (name "Net-(JP10-Pad2)") (class "Default")
      (node (ref "JP10") (pin "2") (pinfunction "2_2") (pintype "passive"))
      (node (ref "PUSH1") (pin "2") (pinfunction "2_2") (pintype "passive"))
      (node (ref "R19") (pin "1") (pinfunction "1_1") (pintype "passive"))
      (node (ref "U$1") (pin "23") (pinfunction "23_23") (pintype "bidirectional"))
    )
    (net (code "70") (name "Net-(JP10-Pad3)") (class "Default")
      (node (ref "JP10") (pin "3") (pinfunction "3_3") (pintype "passive"))
      (node (ref "U$1") (pin "22") (pinfunction "22_22") (pintype "bidirectional"))
    )
    (net (code "71") (name "Net-(JP10-Pad4)") (class "Default")
      (node (ref "JP10") (pin "4") (pinfunction "4_4") (pintype "passive"))
      (node (ref "U$1") (pin "21") (pinfunction "21_21") (pintype "bidirectional"))
    )
    (net (code "72") (name "Net-(JP10-Pad5)") (class "Default")
      (node (ref "JP10") (pin "5") (pinfunction "5_5") (pintype "passive"))
      (node (ref "U$1") (pin "20") (pinfunction "20_20") (pintype "bidirectional"))
    )
    (net (code "73") (name "Net-(JP10-Pad6)") (class "Default")
      (node (ref "JP10") (pin "6") (pinfunction "6_6") (pintype "passive"))
      (node (ref "U$1") (pin "19") (pinfunction "19_19") (pintype "bidirectional"))
    )
    (net (code "74") (name "Net-(JP10-Pad7)") (class "Default")
      (node (ref "JP10") (pin "7") (pinfunction "7_7") (pintype "passive"))
      (node (ref "U$1") (pin "18") (pinfunction "18_18") (pintype "bidirectional"))
    )
    (net (code "75") (name "Net-(JP10-Pad8)") (class "Default")
      (node (ref "JP10") (pin "8") (pinfunction "8_8") (pintype "passive"))
      (node (ref "U$1") (pin "17") (pinfunction "17_17") (pintype "bidirectional"))
    )
    (net (code "76") (name "Net-(LED1-PadA)") (class "Default")
      (node (ref "LED1") (pin "A") (pinfunction "A_A") (pintype "passive"))
      (node (ref "R15") (pin "2") (pinfunction "2_2") (pintype "passive"))
    )
    (net (code "77") (name "Net-(LED2-PadA)") (class "Default")
      (node (ref "LED2") (pin "A") (pinfunction "A_A") (pintype "passive"))
      (node (ref "R16") (pin "2") (pinfunction "2_2") (pintype "passive"))
    )
    (net (code "78") (name "Net-(LED3-PadA)") (class "Default")
      (node (ref "LED3") (pin "A") (pinfunction "A_A") (pintype "passive"))
      (node (ref "R13") (pin "2") (pinfunction "2_2") (pintype "passive"))
    )
    (net (code "79") (name "Net-(LED4-PadA)") (class "Default")
      (node (ref "LED4") (pin "A") (pinfunction "A_A") (pintype "passive"))
      (node (ref "R6") (pin "2") (pinfunction "2_2") (pintype "passive"))
    )
    (net (code "80") (name "Net-(LED5-PadA)") (class "Default")
      (node (ref "LED5") (pin "A") (pinfunction "A_A") (pintype "passive"))
      (node (ref "R7") (pin "2") (pinfunction "2_2") (pintype "passive"))
    )
    (net (code "81") (name "Net-(LED6-PadA)") (class "Default")
      (node (ref "LED6") (pin "A") (pinfunction "A_A") (pintype "passive"))
      (node (ref "R8") (pin "2") (pinfunction "2_2") (pintype "passive"))
    )
    (net (code "82") (name "Net-(LED7-PadA)") (class "Default")
      (node (ref "LED7") (pin "A") (pinfunction "A_A") (pintype "passive"))
      (node (ref "R21") (pin "2") (pinfunction "2_2") (pintype "passive"))
    )
    (net (code "83") (name "Net-(LED8-PadA)") (class "Default")
      (node (ref "LED8") (pin "A") (pinfunction "A_A") (pintype "passive"))
      (node (ref "R11") (pin "2") (pinfunction "2_2") (pintype "passive"))
    )
    (net (code "84") (name "Net-(LED9-PadA)") (class "Default")
      (node (ref "LED9") (pin "A") (pinfunction "A_A") (pintype "passive"))
      (node (ref "R12") (pin "2") (pinfunction "2_2") (pintype "passive"))
    )
    (net (code "85") (name "Net-(LED10-PadC)") (class "Default")
      (node (ref "LED10") (pin "C") (pinfunction "C_C") (pintype "passive"))
      (node (ref "R22") (pin "1") (pinfunction "1_1") (pintype "passive"))
    )
    (net (code "86") (name "Net-(R1-Pad2)") (class "Default")
      (node (ref "R1") (pin "2") (pinfunction "2_2") (pintype "passive"))
      (node (ref "U$1") (pin "79") (pinfunction "79_79") (pintype "bidirectional"))
    )
    (net (code "87") (name "Net-(R3-Pad2)") (class "Default")
      (node (ref "R3") (pin "2") (pinfunction "2_2") (pintype "passive"))
      (node (ref "R4") (pin "1") (pinfunction "1_1") (pintype "passive"))
      (node (ref "R5") (pin "1") (pinfunction "1_1") (pintype "passive"))
      (node (ref "U$1") (pin "77") (pinfunction "77_77") (pintype "bidirectional"))
    )
    (net (code "88") (name "Net-(R6-Pad1)") (class "Default")
      (node (ref "R6") (pin "1") (pinfunction "1_1") (pintype "passive"))
      (node (ref "U$1") (pin "39") (pinfunction "39_39") (pintype "bidirectional"))
    )
    (net (code "89") (name "Net-(R7-Pad1)") (class "Default")
      (node (ref "R7") (pin "1") (pinfunction "1_1") (pintype "passive"))
      (node (ref "U$1") (pin "37") (pinfunction "37_37") (pintype "bidirectional"))
    )
    (net (code "90") (name "Net-(R8-Pad1)") (class "Default")
      (node (ref "R8") (pin "1") (pinfunction "1_1") (pintype "passive"))
      (node (ref "U$1") (pin "38") (pinfunction "38_38") (pintype "bidirectional"))
    )
    (net (code "91") (name "Net-(R10-Pad1)") (class "Default")
      (node (ref "R10") (pin "1") (pinfunction "1_1") (pintype "passive"))
      (node (ref "SJ1") (pin "1") (pinfunction "1_1") (pintype "passive"))
    )
    (net (code "92") (name "Net-(R10-Pad2)") (class "Default")
      (node (ref "R10") (pin "2") (pinfunction "2_2") (pintype "passive"))
      (node (ref "R5") (pin "2") (pinfunction "2_2") (pintype "passive"))
      (node (ref "U$1") (pin "78") (pinfunction "78_78") (pintype "bidirectional"))
    )
    (net (code "93") (name "Net-(R11-Pad1)") (class "Default")
      (node (ref "R11") (pin "1") (pinfunction "1_1") (pintype "passive"))
      (node (ref "U$1") (pin "40") (pinfunction "40_40") (pintype "bidirectional"))
    )
    (net (code "94") (name "Net-(R12-Pad1)") (class "Default")
      (node (ref "R12") (pin "1") (pinfunction "1_1") (pintype "passive"))
      (node (ref "U$1") (pin "41") (pinfunction "41_41") (pintype "bidirectional"))
    )
    (net (code "95") (name "Net-(R13-Pad1)") (class "Default")
      (node (ref "R13") (pin "1") (pinfunction "1_1") (pintype "passive"))
      (node (ref "U$1") (pin "36") (pinfunction "36_36") (pintype "bidirectional"))
    )
    (net (code "96") (name "Net-(R16-Pad1)") (class "Default")
      (node (ref "R16") (pin "1") (pinfunction "1_1") (pintype "passive"))
      (node (ref "U$1") (pin "35") (pinfunction "35_35") (pintype "bidirectional"))
    )
    (net (code "97") (name "VCC") (class "Default")
      (node (ref "C14") (pin "1") (pinfunction "1_1") (pintype "passive"))
      (node (ref "C2") (pin "2") (pinfunction "2_2") (pintype "passive"))
      (node (ref "C20") (pin "+") (pinfunction "+_+") (pintype "passive"))
      (node (ref "C24") (pin "2") (pinfunction "2_2") (pintype "passive"))
      (node (ref "C3") (pin "1") (pinfunction "1_1") (pintype "passive"))
      (node (ref "C4") (pin "2") (pinfunction "2_2") (pintype "passive"))
      (node (ref "C5") (pin "1") (pinfunction "1_1") (pintype "passive"))
      (node (ref "JP1") (pin "1") (pinfunction "1_1") (pintype "passive"))
      (node (ref "JP3") (pin "1") (pinfunction "1_1") (pintype "passive"))
      (node (ref "JP4") (pin "2") (pinfunction "2_2") (pintype "passive"))
      (node (ref "L2") (pin "2") (pinfunction "2_2") (pintype "passive"))
      (node (ref "LED10") (pin "A") (pinfunction "A_A") (pintype "passive"))
      (node (ref "PUSH1") (pin "1") (pinfunction "1_1") (pintype "passive"))
      (node (ref "PUSH2") (pin "1") (pinfunction "1_1") (pintype "passive"))
      (node (ref "R2") (pin "1") (pinfunction "1_1") (pintype "passive"))
      (node (ref "R23") (pin "1") (pinfunction "1_1") (pintype "passive"))
      (node (ref "R24") (pin "1") (pinfunction "1_1") (pintype "passive"))
      (node (ref "U$1") (pin "25") (pinfunction "25_25") (pintype "power_in"))
      (node (ref "U$1") (pin "64") (pinfunction "64_64") (pintype "power_in"))
      (node (ref "U$1") (pin "87") (pinfunction "87_87") (pintype "bidirectional"))
      (node (ref "U$1") (pin "89") (pinfunction "89_89") (pintype "power_in"))
    )
    (net (code "98") (name "unconnected-(H1-Pad1)") (class "Default")
      (node (ref "H1") (pin "1") (pinfunction "1_1") (pintype "passive"))
    )
    (net (code "99") (name "unconnected-(H2-Pad1)") (class "Default")
      (node (ref "H2") (pin "1") (pinfunction "1_1") (pintype "passive"))
    )
    (net (code "100") (name "unconnected-(H3-Pad1)") (class "Default")
      (node (ref "H3") (pin "1") (pinfunction "1_1") (pintype "passive"))
    )
    (net (code "101") (name "unconnected-(H4-Pad1)") (class "Default")
      (node (ref "H4") (pin "1") (pinfunction "1_1") (pintype "passive"))
    )
    (net (code "102") (name "unconnected-(U$1-Pad16)") (class "Default")
      (node (ref "U$1") (pin "16") (pinfunction "16_16") (pintype "bidirectional"))
    )
    (net (code "103") (name "unconnected-(U$1-Pad28)") (class "Default")
      (node (ref "U$1") (pin "28") (pinfunction "28_28") (pintype "bidirectional"))
    )
    (net (code "104") (name "unconnected-(U$1-Pad30)") (class "Default")
      (node (ref "U$1") (pin "30") (pinfunction "30_30") (pintype "bidirectional"))
    )
    (net (code "105") (name "unconnected-(U$1-Pad31)") (class "Default")
      (node (ref "U$1") (pin "31") (pinfunction "31_31") (pintype "bidirectional"))
    )
    (net (code "106") (name "unconnected-(U$1-Pad32)") (class "Default")
      (node (ref "U$1") (pin "32") (pinfunction "32_32") (pintype "bidirectional"))
    )
    (net (code "107") (name "unconnected-(U$1-Pad33)") (class "Default")
      (node (ref "U$1") (pin "33") (pinfunction "33_33") (pintype "bidirectional"))
    )
    (net (code "108") (name "unconnected-(U$1-Pad88)") (class "Default")
      (node (ref "U$1") (pin "88") (pinfunction "88_88") (pintype "bidirectional"))
    )
  )
)
